# MCU.net
KiCad netlist of a schematic drawn in Altium Designer
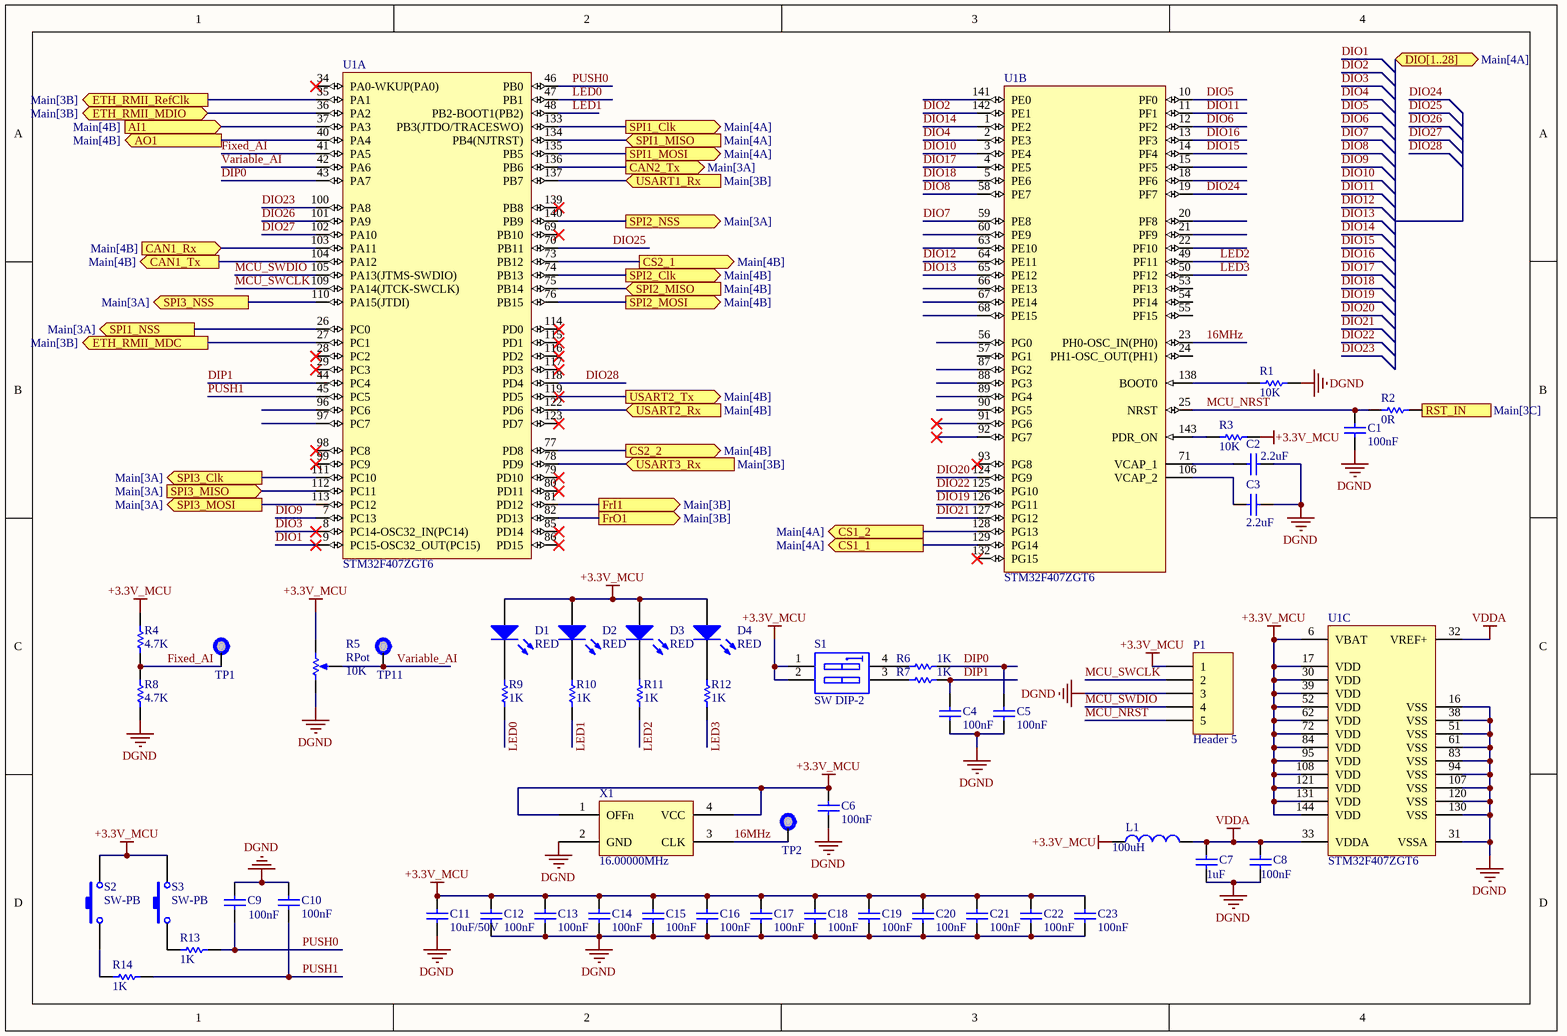
[diagram p0: MCU.SchDoc]

(export (version "E")
  (design (tool "Eeschema 10.0.6"))
  (components
    (comp (ref "C1")
      (value "100nF")
      (footprint "0603c")
      (description "LOW ESR")
      (fields (field (name "PUBLISHER") "Altium Limited"))
      (libsource (lib "Miscellaneous Devices") (part "Cap"))
    )
    (comp (ref "C2")
      (value "2.2uF")
      (footprint "0805C")
      (description "LOW ESR")
      (fields (field (name "PUBLISHER") "Altium Limited"))
      (libsource (lib "Miscellaneous Devices") (part "Cap"))
    )
    (comp (ref "C3")
      (value "2.2uF")
      (footprint "0805C")
      (description "LOW ESR")
      (fields (field (name "PUBLISHER") "Altium Limited"))
      (libsource (lib "Miscellaneous Devices") (part "Cap"))
    )
    (comp (ref "C4")
      (value "100nF")
      (footprint "0603c")
      (description "LOW ESR")
      (fields (field (name "PUBLISHER") "Altium Limited"))
      (libsource (lib "Miscellaneous Devices") (part "Cap"))
    )
    (comp (ref "C5")
      (value "100nF")
      (footprint "0603c")
      (description "LOW ESR")
      (fields (field (name "PUBLISHER") "Altium Limited"))
      (libsource (lib "Miscellaneous Devices") (part "Cap"))
    )
    (comp (ref "C6")
      (value "100nF")
      (footprint "0603C")
      (description "LOW ESR")
      (fields (field (name "PUBLISHER") "Altium Limited"))
      (libsource (lib "Miscellaneous Devices") (part "Cap"))
    )
    (comp (ref "C7")
      (value "1uF")
      (footprint "0805C")
      (description "LOW ESR")
      (fields (field (name "PUBLISHER") "Altium Limited"))
      (libsource (lib "Miscellaneous Devices") (part "Cap"))
    )
    (comp (ref "C8")
      (value "100nF")
      (footprint "0603C")
      (description "LOW ESR")
      (fields (field (name "PUBLISHER") "Altium Limited"))
      (libsource (lib "Miscellaneous Devices") (part "Cap"))
    )
    (comp (ref "C9")
      (value "100nF")
      (footprint "0603c")
      (description "LOW ESR")
      (fields (field (name "PUBLISHER") "Altium Limited"))
      (libsource (lib "Miscellaneous Devices") (part "Cap"))
    )
    (comp (ref "C10")
      (value "100nF")
      (footprint "0603c")
      (description "LOW ESR")
      (fields (field (name "PUBLISHER") "Altium Limited"))
      (libsource (lib "Miscellaneous Devices") (part "Cap"))
    )
    (comp (ref "C11")
      (value "10uF/50V")
      (footprint "1206C")
      (description "Capacitor")
      (fields (field (name "Comment") "CGA5L1X7R1H106K160AC") (field (name "PUBLISHER") "Altium Limited"))
      (libsource (lib "Miscellaneous Devices") (part "Cap"))
    )
    (comp (ref "C12")
      (value "100nF")
      (footprint "0603C")
      (description "Capacitor")
      (fields (field (name "Comment") "CGA3E2X7R1H104K080AA") (field (name "PUBLISHER") "Altium Limited"))
      (libsource (lib "Miscellaneous Devices") (part "Cap"))
    )
    (comp (ref "C13")
      (value "100nF")
      (footprint "0603C")
      (description "Capacitor")
      (fields (field (name "Comment") "CGA3E2X7R1H104K080AA") (field (name "PUBLISHER") "Altium Limited"))
      (libsource (lib "Miscellaneous Devices") (part "Cap"))
    )
    (comp (ref "C14")
      (value "100nF")
      (footprint "0603C")
      (description "Capacitor")
      (fields (field (name "Comment") "CGA3E2X7R1H104K080AA") (field (name "PUBLISHER") "Altium Limited"))
      (libsource (lib "Miscellaneous Devices") (part "Cap"))
    )
    (comp (ref "C15")
      (value "100nF")
      (footprint "0603C")
      (description "Capacitor")
      (fields (field (name "Comment") "CGA3E2X7R1H104K080AA") (field (name "PUBLISHER") "Altium Limited"))
      (libsource (lib "Miscellaneous Devices") (part "Cap"))
    )
    (comp (ref "C16")
      (value "100nF")
      (footprint "0603C")
      (description "Capacitor")
      (fields (field (name "Comment") "CGA3E2X7R1H104K080AA") (field (name "PUBLISHER") "Altium Limited"))
      (libsource (lib "Miscellaneous Devices") (part "Cap"))
    )
    (comp (ref "C17")
      (value "100nF")
      (footprint "0603C")
      (description "Capacitor")
      (fields (field (name "Comment") "CGA3E2X7R1H104K080AA") (field (name "PUBLISHER") "Altium Limited"))
      (libsource (lib "Miscellaneous Devices") (part "Cap"))
    )
    (comp (ref "C18")
      (value "100nF")
      (footprint "0603C")
      (description "Capacitor")
      (fields (field (name "Comment") "CGA3E2X7R1H104K080AA") (field (name "PUBLISHER") "Altium Limited"))
      (libsource (lib "Miscellaneous Devices") (part "Cap"))
    )
    (comp (ref "C19")
      (value "100nF")
      (footprint "0603C")
      (description "Capacitor")
      (fields (field (name "Comment") "CGA3E2X7R1H104K080AA") (field (name "PUBLISHER") "Altium Limited"))
      (libsource (lib "Miscellaneous Devices") (part "Cap"))
    )
    (comp (ref "C20")
      (value "100nF")
      (footprint "0603C")
      (description "Capacitor")
      (fields (field (name "Comment") "CGA3E2X7R1H104K080AA") (field (name "PUBLISHER") "Altium Limited"))
      (libsource (lib "Miscellaneous Devices") (part "Cap"))
    )
    (comp (ref "C21")
      (value "100nF")
      (footprint "0603C")
      (description "Capacitor")
      (fields (field (name "Comment") "CGA3E2X7R1H104K080AA") (field (name "PUBLISHER") "Altium Limited"))
      (libsource (lib "Miscellaneous Devices") (part "Cap"))
    )
    (comp (ref "C22")
      (value "100nF")
      (footprint "0603C")
      (description "Capacitor")
      (fields (field (name "Comment") "CGA3E2X7R1H104K080AA") (field (name "PUBLISHER") "Altium Limited"))
      (libsource (lib "Miscellaneous Devices") (part "Cap"))
    )
    (comp (ref "C23")
      (value "100nF")
      (footprint "0603C")
      (description "Capacitor")
      (fields (field (name "Comment") "CGA3E2X7R1H104K080AA") (field (name "PUBLISHER") "Altium Limited"))
      (libsource (lib "Miscellaneous Devices") (part "Cap"))
    )
    (comp (ref "D1")
      (value "RED")
      (footprint "0805LED")
      (description "Typical INFRARED GaAs LED")
      (fields (field (name "PUBLISHER") "Altium Limited"))
      (libsource (lib "Miscellaneous Devices") (part "LED0"))
    )
    (comp (ref "D2")
      (value "RED")
      (footprint "0805LED")
      (description "Typical INFRARED GaAs LED")
      (fields (field (name "PUBLISHER") "Altium Limited"))
      (libsource (lib "Miscellaneous Devices") (part "LED0"))
    )
    (comp (ref "D3")
      (value "RED")
      (footprint "0805LED")
      (description "Typical INFRARED GaAs LED")
      (fields (field (name "PUBLISHER") "Altium Limited"))
      (libsource (lib "Miscellaneous Devices") (part "LED0"))
    )
    (comp (ref "D4")
      (value "RED")
      (footprint "0805LED")
      (description "Typical INFRARED GaAs LED")
      (fields (field (name "PUBLISHER") "Altium Limited"))
      (libsource (lib "Miscellaneous Devices") (part "LED0"))
    )
    (comp (ref "L1")
      (value "100uH")
      (footprint "0805FB")
      (description "Inductor")
      (fields (field (name "PUBLISHER") "Altium Limited"))
      (libsource (lib "Miscellaneous Devices") (part "Inductor"))
    )
    (comp (ref "P1")
      (value "Header 5")
      (footprint "HDR1X5")
      (description "Header, 5-Pin")
      (fields (field (name "PUBLISHER") "Altium Limited"))
      (libsource (lib "Miscellaneous Connectors") (part "Header 5"))
    )
    (comp (ref "R1")
      (value "10K")
      (footprint "0805")
      (description "Resistor")
      (fields (field (name "Comment") "Res1") (field (name "PUBLISHER") "Altium Limited"))
      (libsource (lib "Miscellaneous Devices") (part "Res1"))
    )
    (comp (ref "R2")
      (value "0R")
      (footprint "0805")
      (description "Resistor")
      (fields (field (name "Comment") "Res1") (field (name "PUBLISHER") "Altium Limited"))
      (libsource (lib "Miscellaneous Devices") (part "Res1"))
    )
    (comp (ref "R3")
      (value "10K")
      (footprint "0805")
      (description "Resistor")
      (fields (field (name "Comment") "Res1") (field (name "PUBLISHER") "Altium Limited"))
      (libsource (lib "Miscellaneous Devices") (part "Res1"))
    )
    (comp (ref "R4")
      (value "4.7K")
      (footprint "0805")
      (description "Resistor")
      (fields (field (name "Comment") "Res1") (field (name "PUBLISHER") "Altium Limited"))
      (libsource (lib "Miscellaneous Devices") (part "Res1"))
    )
    (comp (ref "R5")
      (value "RPot")
      (footprint "POT-MULTITURN")
      (description "Potentiometer")
      (fields (field (name "ALTIUM_VALUE") "10K") (field (name "PUBLISHER") "Altium Limited"))
      (libsource (lib "Miscellaneous Devices") (part "RPot"))
    )
    (comp (ref "R6")
      (value "1K")
      (footprint "0805")
      (description "Resistor")
      (fields (field (name "Comment") "Res1") (field (name "PUBLISHER") "Altium Limited"))
      (libsource (lib "Miscellaneous Devices") (part "Res1"))
    )
    (comp (ref "R7")
      (value "1K")
      (footprint "0805")
      (description "Resistor")
      (fields (field (name "Comment") "Res1") (field (name "PUBLISHER") "Altium Limited"))
      (libsource (lib "Miscellaneous Devices") (part "Res1"))
    )
    (comp (ref "R8")
      (value "4.7K")
      (footprint "0805")
      (description "Resistor")
      (fields (field (name "Comment") "Res1") (field (name "PUBLISHER") "Altium Limited"))
      (libsource (lib "Miscellaneous Devices") (part "Res1"))
    )
    (comp (ref "R9")
      (value "1K")
      (footprint "0805")
      (description "Resistor")
      (fields (field (name "Comment") "Res1") (field (name "PUBLISHER") "Altium Limited"))
      (libsource (lib "Miscellaneous Devices") (part "Res1"))
    )
    (comp (ref "R10")
      (value "1K")
      (footprint "0805")
      (description "Resistor")
      (fields (field (name "Comment") "Res1") (field (name "PUBLISHER") "Altium Limited"))
      (libsource (lib "Miscellaneous Devices") (part "Res1"))
    )
    (comp (ref "R11")
      (value "1K")
      (footprint "0805")
      (description "Resistor")
      (fields (field (name "Comment") "Res1") (field (name "PUBLISHER") "Altium Limited"))
      (libsource (lib "Miscellaneous Devices") (part "Res1"))
    )
    (comp (ref "R12")
      (value "1K")
      (footprint "0805")
      (description "Resistor")
      (fields (field (name "Comment") "Res1") (field (name "PUBLISHER") "Altium Limited"))
      (libsource (lib "Miscellaneous Devices") (part "Res1"))
    )
    (comp (ref "R13")
      (value "1K")
      (footprint "0805")
      (description "Resistor")
      (fields (field (name "Comment") "Res1") (field (name "PUBLISHER") "Altium Limited"))
      (libsource (lib "Miscellaneous Devices") (part "Res1"))
    )
    (comp (ref "R14")
      (value "1K")
      (footprint "0805")
      (description "Resistor")
      (fields (field (name "Comment") "Res1") (field (name "PUBLISHER") "Altium Limited"))
      (libsource (lib "Miscellaneous Devices") (part "Res1"))
    )
    (comp (ref "S1")
      (value "SW DIP-2")
      (footprint "DIP-4")
      (description "DIP Switch, 2 Position, SPST")
      (fields (field (name "PUBLISHER") "Altium Limited"))
      (libsource (lib "Miscellaneous Devices") (part "SW DIP-2"))
    )
    (comp (ref "S2")
      (value "SW-PB")
      (footprint "PUSHBUTTON-SMD")
      (description "Switch")
      (fields (field (name "PUBLISHER") "Altium Limited"))
      (libsource (lib "Miscellaneous Devices") (part "SW-PB"))
    )
    (comp (ref "S3")
      (value "SW-PB")
      (footprint "PUSHBUTTON-SMD")
      (description "Switch")
      (fields (field (name "PUBLISHER") "Altium Limited"))
      (libsource (lib "Miscellaneous Devices") (part "SW-PB"))
    )
    (comp (ref "TP1") (value "TestPoint") (footprint "TP") (libsource (lib "SchlibV0.1") (part "TestPoint")))
    (comp (ref "TP2") (value "TestPoint") (footprint "TP") (libsource (lib "SchlibV0.1") (part "TestPoint")))
    (comp (ref "TP11") (value "TestPoint") (footprint "TP") (libsource (lib "SchlibV0.1") (part "TestPoint")))
    (comp (ref "U1")
      (value "STM32F407ZGT6")
      (footprint "STM-LQFP144_N")
      (fields (field (name "MANUFACTURER") "STMicroelectronics"))
      (libsource (lib "STMicroelectronics STM32 F4") (part "STM32F407ZGT6"))
    )
    (comp (ref "X1")
      (value "16.00000MHz")
      (footprint "OSC-SMT")
      (fields (field (name "Comment") "SG-8018CB 16.000000 MHZ TJHPA"))
      (libsource (lib "TMS320F2812-PGF") (part "Oscillator"))
    )
  )
  (nets
    (net (code "1") (name "+3.3V_MCU") (class "Default")
      (node (ref "C11") (pin "2") (pinfunction "2_2") (pintype "passive"))
      (node (ref "C12") (pin "1") (pinfunction "1_1") (pintype "passive"))
      (node (ref "C13") (pin "1") (pinfunction "1_1") (pintype "passive"))
      (node (ref "C14") (pin "1") (pinfunction "1_1") (pintype "passive"))
      (node (ref "C15") (pin "1") (pinfunction "1_1") (pintype "passive"))
      (node (ref "C16") (pin "1") (pinfunction "1_1") (pintype "passive"))
      (node (ref "C17") (pin "1") (pinfunction "1_1") (pintype "passive"))
      (node (ref "C18") (pin "1") (pinfunction "1_1") (pintype "passive"))
      (node (ref "C19") (pin "1") (pinfunction "1_1") (pintype "passive"))
      (node (ref "C20") (pin "1") (pinfunction "1_1") (pintype "passive"))
      (node (ref "C21") (pin "1") (pinfunction "1_1") (pintype "passive"))
      (node (ref "C22") (pin "1") (pinfunction "1_1") (pintype "passive"))
      (node (ref "C23") (pin "1") (pinfunction "1_1") (pintype "passive"))
      (node (ref "C6") (pin "1") (pinfunction "1_1") (pintype "passive"))
      (node (ref "D1") (pin "1") (pinfunction "A_1") (pintype "passive"))
      (node (ref "D2") (pin "1") (pinfunction "A_1") (pintype "passive"))
      (node (ref "D3") (pin "1") (pinfunction "A_1") (pintype "passive"))
      (node (ref "D4") (pin "1") (pinfunction "A_1") (pintype "passive"))
      (node (ref "L1") (pin "1") (pinfunction "1_1") (pintype "passive"))
      (node (ref "P1") (pin "1") (pinfunction "1_1") (pintype "passive"))
      (node (ref "R3") (pin "1") (pinfunction "1_1") (pintype "passive"))
      (node (ref "R4") (pin "2") (pinfunction "2_2") (pintype "passive"))
      (node (ref "R5") (pin "3") (pinfunction "BOT_3") (pintype "passive"))
      (node (ref "S1") (pin "1") (pinfunction "A1_1") (pintype "passive"))
      (node (ref "S1") (pin "2") (pinfunction "A2_2") (pintype "passive"))
      (node (ref "S2") (pin "2") (pinfunction "2_2") (pintype "passive"))
      (node (ref "S3") (pin "2") (pinfunction "2_2") (pintype "passive"))
      (node (ref "U1") (pin "108") (pinfunction "VDD_108") (pintype "power_in"))
      (node (ref "U1") (pin "121") (pinfunction "VDD_121") (pintype "power_in"))
      (node (ref "U1") (pin "131") (pinfunction "VDD_131") (pintype "power_in"))
      (node (ref "U1") (pin "144") (pinfunction "VDD_144") (pintype "power_in"))
      (node (ref "U1") (pin "17") (pinfunction "VDD_17") (pintype "power_in"))
      (node (ref "U1") (pin "30") (pinfunction "VDD_30") (pintype "power_in"))
      (node (ref "U1") (pin "39") (pinfunction "VDD_39") (pintype "power_in"))
      (node (ref "U1") (pin "52") (pinfunction "VDD_52") (pintype "power_in"))
      (node (ref "U1") (pin "6") (pinfunction "VBAT_6") (pintype "power_in"))
      (node (ref "U1") (pin "62") (pinfunction "VDD_62") (pintype "power_in"))
      (node (ref "U1") (pin "72") (pinfunction "VDD_72") (pintype "power_in"))
      (node (ref "U1") (pin "84") (pinfunction "VDD_84") (pintype "power_in"))
      (node (ref "U1") (pin "95") (pinfunction "VDD_95") (pintype "power_in"))
      (node (ref "X1") (pin "1") (pinfunction "OFFn_1") (pintype "passive"))
      (node (ref "X1") (pin "4") (pinfunction "VCC_4") (pintype "passive"))
    )
    (net (code "2") (name "/16MHz") (class "Default")
      (node (ref "TP2") (pin "1") (pintype "passive"))
      (node (ref "U1") (pin "23") (pinfunction "PH0-OSC_IN(PH0)_23") (pintype "bidirectional"))
      (node (ref "X1") (pin "3") (pinfunction "CLK_3") (pintype "passive"))
    )
    (net (code "3") (name "/AI1") (class "Default")
      (node (ref "U1") (pin "37") (pinfunction "PA3_37") (pintype "bidirectional"))
    )
    (net (code "4") (name "/AO1") (class "Default")
      (node (ref "U1") (pin "40") (pinfunction "PA4_40") (pintype "bidirectional"))
    )
    (net (code "5") (name "/CAN1_Rx") (class "Default")
      (node (ref "U1") (pin "103") (pinfunction "PA11_103") (pintype "bidirectional"))
    )
    (net (code "6") (name "/CAN1_Tx") (class "Default")
      (node (ref "U1") (pin "104") (pinfunction "PA12_104") (pintype "bidirectional"))
    )
    (net (code "7") (name "/CAN2_Tx") (class "Default")
      (node (ref "U1") (pin "136") (pinfunction "PB6_136") (pintype "bidirectional"))
    )
    (net (code "8") (name "/CS1_1") (class "Default")
      (node (ref "U1") (pin "129") (pinfunction "PG14_129") (pintype "bidirectional"))
    )
    (net (code "9") (name "/CS1_2") (class "Default")
      (node (ref "U1") (pin "128") (pinfunction "PG13_128") (pintype "bidirectional"))
    )
    (net (code "10") (name "/CS2_1") (class "Default")
      (node (ref "U1") (pin "73") (pinfunction "PB12_73") (pintype "bidirectional"))
    )
    (net (code "11") (name "/CS2_2") (class "Default")
      (node (ref "U1") (pin "77") (pinfunction "PD8_77") (pintype "bidirectional"))
    )
    (net (code "12") (name "/DIO1") (class "Default")
      (node (ref "U1") (pin "9") (pinfunction "PC15-OSC32_OUT(PC15)_9") (pintype "bidirectional+no_connect"))
    )
    (net (code "13") (name "/DIO2") (class "Default")
      (node (ref "U1") (pin "142") (pinfunction "PE1_142") (pintype "bidirectional"))
    )
    (net (code "14") (name "/DIO3") (class "Default")
      (node (ref "U1") (pin "8") (pinfunction "PC14-OSC32_IN(PC14)_8") (pintype "bidirectional+no_connect"))
    )
    (net (code "15") (name "/DIO4") (class "Default")
      (node (ref "U1") (pin "2") (pinfunction "PE3_2") (pintype "bidirectional"))
    )
    (net (code "16") (name "/DIO5") (class "Default")
      (node (ref "U1") (pin "10") (pinfunction "PF0_10") (pintype "bidirectional"))
    )
    (net (code "17") (name "/DIO6") (class "Default")
      (node (ref "U1") (pin "12") (pinfunction "PF2_12") (pintype "bidirectional"))
    )
    (net (code "18") (name "/DIO7") (class "Default")
      (node (ref "U1") (pin "59") (pinfunction "PE8_59") (pintype "bidirectional"))
    )
    (net (code "19") (name "/DIO8") (class "Default")
      (node (ref "U1") (pin "58") (pinfunction "PE7_58") (pintype "bidirectional"))
    )
    (net (code "20") (name "/DIO9") (class "Default")
      (node (ref "U1") (pin "7") (pinfunction "PC13_7") (pintype "bidirectional"))
    )
    (net (code "21") (name "/DIO10") (class "Default")
      (node (ref "U1") (pin "3") (pinfunction "PE4_3") (pintype "bidirectional"))
    )
    (net (code "22") (name "/DIO11") (class "Default")
      (node (ref "U1") (pin "11") (pinfunction "PF1_11") (pintype "bidirectional"))
    )
    (net (code "23") (name "/DIO12") (class "Default")
      (node (ref "U1") (pin "64") (pinfunction "PE11_64") (pintype "bidirectional"))
    )
    (net (code "24") (name "/DIO13") (class "Default")
      (node (ref "U1") (pin "65") (pinfunction "PE12_65") (pintype "bidirectional"))
    )
    (net (code "25") (name "/DIO14") (class "Default")
      (node (ref "U1") (pin "1") (pinfunction "PE2_1") (pintype "bidirectional"))
    )
    (net (code "26") (name "/DIO15") (class "Default")
      (node (ref "U1") (pin "14") (pinfunction "PF4_14") (pintype "bidirectional"))
    )
    (net (code "27") (name "/DIO16") (class "Default")
      (node (ref "U1") (pin "13") (pinfunction "PF3_13") (pintype "bidirectional"))
    )
    (net (code "28") (name "/DIO17") (class "Default")
      (node (ref "U1") (pin "4") (pinfunction "PE5_4") (pintype "bidirectional"))
    )
    (net (code "29") (name "/DIO18") (class "Default")
      (node (ref "U1") (pin "5") (pinfunction "PE6_5") (pintype "bidirectional"))
    )
    (net (code "30") (name "/DIO19") (class "Default")
      (node (ref "U1") (pin "126") (pinfunction "PG11_126") (pintype "bidirectional"))
    )
    (net (code "31") (name "/DIO20") (class "Default")
      (node (ref "U1") (pin "124") (pinfunction "PG9_124") (pintype "bidirectional"))
    )
    (net (code "32") (name "/DIO21") (class "Default")
      (node (ref "U1") (pin "127") (pinfunction "PG12_127") (pintype "bidirectional"))
    )
    (net (code "33") (name "/DIO22") (class "Default")
      (node (ref "U1") (pin "125") (pinfunction "PG10_125") (pintype "bidirectional"))
    )
    (net (code "34") (name "/DIO23") (class "Default")
      (node (ref "U1") (pin "100") (pinfunction "PA8_100") (pintype "bidirectional"))
    )
    (net (code "35") (name "/DIO24") (class "Default")
      (node (ref "U1") (pin "19") (pinfunction "PF7_19") (pintype "bidirectional"))
    )
    (net (code "36") (name "/DIO25") (class "Default")
      (node (ref "U1") (pin "70") (pinfunction "PB11_70") (pintype "bidirectional"))
    )
    (net (code "37") (name "/DIO26") (class "Default")
      (node (ref "U1") (pin "101") (pinfunction "PA9_101") (pintype "bidirectional"))
    )
    (net (code "38") (name "/DIO27") (class "Default")
      (node (ref "U1") (pin "102") (pinfunction "PA10_102") (pintype "bidirectional"))
    )
    (net (code "39") (name "/DIO28") (class "Default")
      (node (ref "U1") (pin "118") (pinfunction "PD4_118") (pintype "bidirectional"))
    )
    (net (code "41") (name "/DIP0") (class "Default")
      (node (ref "C5") (pin "1") (pinfunction "1_1") (pintype "passive"))
      (node (ref "R6") (pin "2") (pinfunction "2_2") (pintype "passive"))
      (node (ref "U1") (pin "43") (pinfunction "PA7_43") (pintype "bidirectional"))
    )
    (net (code "42") (name "/DIP1") (class "Default")
      (node (ref "C4") (pin "1") (pinfunction "1_1") (pintype "passive"))
      (node (ref "R7") (pin "2") (pinfunction "2_2") (pintype "passive"))
      (node (ref "U1") (pin "44") (pinfunction "PC4_44") (pintype "bidirectional"))
    )
    (net (code "43") (name "/ETH_RMII_MDC") (class "Default")
      (node (ref "U1") (pin "27") (pinfunction "PC1_27") (pintype "bidirectional"))
    )
    (net (code "44") (name "/ETH_RMII_MDIO") (class "Default")
      (node (ref "U1") (pin "36") (pinfunction "PA2_36") (pintype "bidirectional"))
    )
    (net (code "45") (name "/ETH_RMII_RefClk") (class "Default")
      (node (ref "U1") (pin "35") (pinfunction "PA1_35") (pintype "bidirectional"))
    )
    (net (code "46") (name "/Fixed_AI") (class "Default")
      (node (ref "R4") (pin "1") (pinfunction "1_1") (pintype "passive"))
      (node (ref "R8") (pin "2") (pinfunction "2_2") (pintype "passive"))
      (node (ref "TP1") (pin "1") (pintype "passive"))
      (node (ref "U1") (pin "41") (pinfunction "PA5_41") (pintype "bidirectional"))
    )
    (net (code "47") (name "/FrI1") (class "Default")
      (node (ref "U1") (pin "81") (pinfunction "PD12_81") (pintype "bidirectional"))
    )
    (net (code "48") (name "/FrO1") (class "Default")
      (node (ref "U1") (pin "82") (pinfunction "PD13_82") (pintype "bidirectional"))
    )
    (net (code "49") (name "/LED0") (class "Default")
      (node (ref "R9") (pin "1") (pinfunction "1_1") (pintype "passive"))
      (node (ref "U1") (pin "47") (pinfunction "PB1_47") (pintype "bidirectional"))
    )
    (net (code "50") (name "/LED1") (class "Default")
      (node (ref "R10") (pin "1") (pinfunction "1_1") (pintype "passive"))
      (node (ref "U1") (pin "48") (pinfunction "PB2-BOOT1(PB2)_48") (pintype "bidirectional"))
    )
    (net (code "51") (name "/LED2") (class "Default")
      (node (ref "R11") (pin "1") (pinfunction "1_1") (pintype "passive"))
      (node (ref "U1") (pin "49") (pinfunction "PF11_49") (pintype "bidirectional"))
    )
    (net (code "52") (name "/LED3") (class "Default")
      (node (ref "R12") (pin "1") (pinfunction "1_1") (pintype "passive"))
      (node (ref "U1") (pin "50") (pinfunction "PF12_50") (pintype "bidirectional"))
    )
    (net (code "53") (name "/MCU_NRST") (class "Default")
      (node (ref "C1") (pin "1") (pinfunction "1_1") (pintype "passive"))
      (node (ref "P1") (pin "5") (pinfunction "5_5") (pintype "passive"))
      (node (ref "R2") (pin "2") (pinfunction "2_2") (pintype "passive"))
      (node (ref "U1") (pin "25") (pinfunction "NRST_25") (pintype "bidirectional"))
    )
    (net (code "54") (name "/MCU_SWCLK") (class "Default")
      (node (ref "P1") (pin "2") (pinfunction "2_2") (pintype "passive"))
      (node (ref "U1") (pin "109") (pinfunction "PA14(JTCK-SWCLK)_109") (pintype "bidirectional"))
    )
    (net (code "55") (name "/MCU_SWDIO") (class "Default")
      (node (ref "P1") (pin "4") (pinfunction "4_4") (pintype "passive"))
      (node (ref "U1") (pin "105") (pinfunction "PA13(JTMS-SWDIO)_105") (pintype "bidirectional"))
    )
    (net (code "56") (name "/PUSH0") (class "Default")
      (node (ref "C9") (pin "2") (pinfunction "2_2") (pintype "passive"))
      (node (ref "R13") (pin "2") (pinfunction "2_2") (pintype "passive"))
      (node (ref "U1") (pin "46") (pinfunction "PB0_46") (pintype "bidirectional"))
    )
    (net (code "57") (name "/PUSH1") (class "Default")
      (node (ref "C10") (pin "2") (pinfunction "2_2") (pintype "passive"))
      (node (ref "R14") (pin "1") (pinfunction "1_1") (pintype "passive"))
      (node (ref "U1") (pin "45") (pinfunction "PC5_45") (pintype "bidirectional"))
    )
    (net (code "58") (name "/RST_IN") (class "Default")
      (node (ref "R2") (pin "1") (pinfunction "1_1") (pintype "passive"))
    )
    (net (code "59") (name "/SPI1_Clk") (class "Default")
      (node (ref "U1") (pin "133") (pinfunction "PB3(JTDO/TRACESWO)_133") (pintype "bidirectional"))
    )
    (net (code "60") (name "/SPI1_MISO") (class "Default")
      (node (ref "U1") (pin "134") (pinfunction "PB4(NJTRST)_134") (pintype "bidirectional"))
    )
    (net (code "61") (name "/SPI1_MOSI") (class "Default")
      (node (ref "U1") (pin "135") (pinfunction "PB5_135") (pintype "bidirectional"))
    )
    (net (code "62") (name "/SPI1_NSS") (class "Default")
      (node (ref "U1") (pin "26") (pinfunction "PC0_26") (pintype "bidirectional"))
    )
    (net (code "63") (name "/SPI2_Clk") (class "Default")
      (node (ref "U1") (pin "74") (pinfunction "PB13_74") (pintype "bidirectional"))
    )
    (net (code "64") (name "/SPI2_MISO") (class "Default")
      (node (ref "U1") (pin "75") (pinfunction "PB14_75") (pintype "bidirectional"))
    )
    (net (code "65") (name "/SPI2_MOSI") (class "Default")
      (node (ref "U1") (pin "76") (pinfunction "PB15_76") (pintype "bidirectional"))
    )
    (net (code "66") (name "/SPI2_NSS") (class "Default")
      (node (ref "U1") (pin "140") (pinfunction "PB9_140") (pintype "bidirectional"))
    )
    (net (code "67") (name "/SPI3_Clk") (class "Default")
      (node (ref "U1") (pin "111") (pinfunction "PC10_111") (pintype "bidirectional"))
    )
    (net (code "68") (name "/SPI3_MISO") (class "Default")
      (node (ref "U1") (pin "112") (pinfunction "PC11_112") (pintype "bidirectional"))
    )
    (net (code "69") (name "/SPI3_MOSI") (class "Default")
      (node (ref "U1") (pin "113") (pinfunction "PC12_113") (pintype "bidirectional"))
    )
    (net (code "70") (name "/SPI3_NSS") (class "Default")
      (node (ref "U1") (pin "110") (pinfunction "PA15(JTDI)_110") (pintype "bidirectional"))
    )
    (net (code "71") (name "/USART1_Rx") (class "Default")
      (node (ref "U1") (pin "137") (pinfunction "PB7_137") (pintype "bidirectional"))
    )
    (net (code "72") (name "/USART2_Rx") (class "Default")
      (node (ref "U1") (pin "122") (pinfunction "PD6_122") (pintype "bidirectional"))
    )
    (net (code "73") (name "/USART2_Tx") (class "Default")
      (node (ref "U1") (pin "119") (pinfunction "PD5_119") (pintype "bidirectional+no_connect"))
    )
    (net (code "74") (name "/USART3_Rx") (class "Default")
      (node (ref "U1") (pin "78") (pinfunction "PD9_78") (pintype "bidirectional"))
    )
    (net (code "75") (name "/Variable_AI") (class "Default")
      (node (ref "R5") (pin "2") (pinfunction "TAP_2") (pintype "passive"))
      (node (ref "TP11") (pin "1") (pintype "passive"))
      (node (ref "U1") (pin "42") (pinfunction "PA6_42") (pintype "bidirectional"))
    )
    (net (code "76") (name "DGND") (class "Default")
      (node (ref "C1") (pin "2") (pinfunction "2_2") (pintype "passive"))
      (node (ref "C10") (pin "1") (pinfunction "1_1") (pintype "passive"))
      (node (ref "C11") (pin "1") (pinfunction "1_1") (pintype "passive"))
      (node (ref "C12") (pin "2") (pinfunction "2_2") (pintype "passive"))
      (node (ref "C13") (pin "2") (pinfunction "2_2") (pintype "passive"))
      (node (ref "C14") (pin "2") (pinfunction "2_2") (pintype "passive"))
      (node (ref "C15") (pin "2") (pinfunction "2_2") (pintype "passive"))
      (node (ref "C16") (pin "2") (pinfunction "2_2") (pintype "passive"))
      (node (ref "C17") (pin "2") (pinfunction "2_2") (pintype "passive"))
      (node (ref "C18") (pin "2") (pinfunction "2_2") (pintype "passive"))
      (node (ref "C19") (pin "2") (pinfunction "2_2") (pintype "passive"))
      (node (ref "C2") (pin "2") (pinfunction "2_2") (pintype "passive"))
      (node (ref "C20") (pin "2") (pinfunction "2_2") (pintype "passive"))
      (node (ref "C21") (pin "2") (pinfunction "2_2") (pintype "passive"))
      (node (ref "C22") (pin "2") (pinfunction "2_2") (pintype "passive"))
      (node (ref "C23") (pin "2") (pinfunction "2_2") (pintype "passive"))
      (node (ref "C3") (pin "2") (pinfunction "2_2") (pintype "passive"))
      (node (ref "C4") (pin "2") (pinfunction "2_2") (pintype "passive"))
      (node (ref "C5") (pin "2") (pinfunction "2_2") (pintype "passive"))
      (node (ref "C6") (pin "2") (pinfunction "2_2") (pintype "passive"))
      (node (ref "C7") (pin "1") (pinfunction "1_1") (pintype "passive"))
      (node (ref "C8") (pin "1") (pinfunction "1_1") (pintype "passive"))
      (node (ref "C9") (pin "1") (pinfunction "1_1") (pintype "passive"))
      (node (ref "P1") (pin "3") (pinfunction "3_3") (pintype "passive"))
      (node (ref "R1") (pin "1") (pinfunction "1_1") (pintype "passive"))
      (node (ref "R5") (pin "1") (pinfunction "TOP_1") (pintype "passive"))
      (node (ref "R8") (pin "1") (pinfunction "1_1") (pintype "passive"))
      (node (ref "U1") (pin "107") (pinfunction "VSS_107") (pintype "power_in"))
      (node (ref "U1") (pin "120") (pinfunction "VSS_120") (pintype "power_in"))
      (node (ref "U1") (pin "130") (pinfunction "VSS_130") (pintype "power_in"))
      (node (ref "U1") (pin "16") (pinfunction "VSS_16") (pintype "power_in"))
      (node (ref "U1") (pin "31") (pinfunction "VSSA_31") (pintype "power_in"))
      (node (ref "U1") (pin "38") (pinfunction "VSS_38") (pintype "power_in"))
      (node (ref "U1") (pin "51") (pinfunction "VSS_51") (pintype "power_in"))
      (node (ref "U1") (pin "61") (pinfunction "VSS_61") (pintype "power_in"))
      (node (ref "U1") (pin "83") (pinfunction "VSS_83") (pintype "power_in"))
      (node (ref "U1") (pin "94") (pinfunction "VSS_94") (pintype "power_in"))
      (node (ref "X1") (pin "2") (pinfunction "GND_2") (pintype "passive"))
    )
    (net (code "77") (name "Net-(D1-K)") (class "Default")
      (node (ref "D1") (pin "2") (pinfunction "K_2") (pintype "passive"))
      (node (ref "R9") (pin "2") (pinfunction "2_2") (pintype "passive"))
    )
    (net (code "78") (name "Net-(D2-K)") (class "Default")
      (node (ref "D2") (pin "2") (pinfunction "K_2") (pintype "passive"))
      (node (ref "R10") (pin "2") (pinfunction "2_2") (pintype "passive"))
    )
    (net (code "79") (name "Net-(D3-K)") (class "Default")
      (node (ref "D3") (pin "2") (pinfunction "K_2") (pintype "passive"))
      (node (ref "R11") (pin "2") (pinfunction "2_2") (pintype "passive"))
    )
    (net (code "80") (name "Net-(D4-K)") (class "Default")
      (node (ref "D4") (pin "2") (pinfunction "K_2") (pintype "passive"))
      (node (ref "R12") (pin "2") (pinfunction "2_2") (pintype "passive"))
    )
    (net (code "81") (name "Net-(R13-Pad1)") (class "Default")
      (node (ref "R13") (pin "1") (pinfunction "1_1") (pintype "passive"))
      (node (ref "S3") (pin "1") (pinfunction "1_1") (pintype "passive"))
    )
    (net (code "82") (name "Net-(R14-Pad2)") (class "Default")
      (node (ref "R14") (pin "2") (pinfunction "2_2") (pintype "passive"))
      (node (ref "S2") (pin "1") (pinfunction "1_1") (pintype "passive"))
    )
    (net (code "83") (name "Net-(S1-B1)") (class "Default")
      (node (ref "R6") (pin "1") (pinfunction "1_1") (pintype "passive"))
      (node (ref "S1") (pin "4") (pinfunction "B1_4") (pintype "passive"))
    )
    (net (code "84") (name "Net-(S1-B2)") (class "Default")
      (node (ref "R7") (pin "1") (pinfunction "1_1") (pintype "passive"))
      (node (ref "S1") (pin "3") (pinfunction "B2_3") (pintype "passive"))
    )
    (net (code "85") (name "Net-(U1B-BOOT0)") (class "Default")
      (node (ref "R1") (pin "2") (pinfunction "2_2") (pintype "passive"))
      (node (ref "U1") (pin "138") (pinfunction "BOOT0_138") (pintype "input"))
    )
    (net (code "86") (name "Net-(U1B-PDR_ON)") (class "Default")
      (node (ref "R3") (pin "2") (pinfunction "2_2") (pintype "passive"))
      (node (ref "U1") (pin "143") (pinfunction "PDR_ON_143") (pintype "input"))
    )
    (net (code "87") (name "Net-(U1B-VCAP_1)") (class "Default")
      (node (ref "C2") (pin "1") (pinfunction "1_1") (pintype "passive"))
      (node (ref "U1") (pin "71") (pinfunction "VCAP_1_71") (pintype "power_in"))
    )
    (net (code "88") (name "Net-(U1B-VCAP_2)") (class "Default")
      (node (ref "C3") (pin "1") (pinfunction "1_1") (pintype "passive"))
      (node (ref "U1") (pin "106") (pinfunction "VCAP_2_106") (pintype "power_in"))
    )
    (net (code "89") (name "VDDA") (class "Default")
      (node (ref "C7") (pin "2") (pinfunction "2_2") (pintype "passive"))
      (node (ref "C8") (pin "2") (pinfunction "2_2") (pintype "passive"))
      (node (ref "L1") (pin "2") (pinfunction "2_2") (pintype "passive"))
      (node (ref "U1") (pin "32") (pinfunction "VREF+_32") (pintype "power_in"))
      (node (ref "U1") (pin "33") (pinfunction "VDDA_33") (pintype "power_in"))
    )
    (net (code "90") (name "unconnected-(U1A-PA0-WKUP(PA0)-Pad34)") (class "Default")
      (node (ref "U1") (pin "34") (pinfunction "PA0-WKUP(PA0)_34") (pintype "bidirectional+no_connect"))
    )
    (net (code "91") (name "unconnected-(U1A-PB8-Pad139)") (class "Default")
      (node (ref "U1") (pin "139") (pinfunction "PB8_139") (pintype "bidirectional+no_connect"))
    )
    (net (code "92") (name "unconnected-(U1A-PB10-Pad69)") (class "Default")
      (node (ref "U1") (pin "69") (pinfunction "PB10_69") (pintype "bidirectional+no_connect"))
    )
    (net (code "93") (name "unconnected-(U1A-PC2-Pad28)") (class "Default")
      (node (ref "U1") (pin "28") (pinfunction "PC2_28") (pintype "bidirectional+no_connect"))
    )
    (net (code "94") (name "unconnected-(U1A-PC3-Pad29)") (class "Default")
      (node (ref "U1") (pin "29") (pinfunction "PC3_29") (pintype "bidirectional+no_connect"))
    )
    (net (code "95") (name "unconnected-(U1A-PC6-Pad96)") (class "Default")
      (node (ref "U1") (pin "96") (pinfunction "PC6_96") (pintype "bidirectional"))
    )
    (net (code "96") (name "unconnected-(U1A-PC7-Pad97)") (class "Default")
      (node (ref "U1") (pin "97") (pinfunction "PC7_97") (pintype "bidirectional"))
    )
    (net (code "97") (name "unconnected-(U1A-PC8-Pad98)") (class "Default")
      (node (ref "U1") (pin "98") (pinfunction "PC8_98") (pintype "bidirectional+no_connect"))
    )
    (net (code "98") (name "unconnected-(U1A-PC9-Pad99)") (class "Default")
      (node (ref "U1") (pin "99") (pinfunction "PC9_99") (pintype "bidirectional+no_connect"))
    )
    (net (code "99") (name "unconnected-(U1A-PD0-Pad114)") (class "Default")
      (node (ref "U1") (pin "114") (pinfunction "PD0_114") (pintype "bidirectional+no_connect"))
    )
    (net (code "100") (name "unconnected-(U1A-PD1-Pad115)") (class "Default")
      (node (ref "U1") (pin "115") (pinfunction "PD1_115") (pintype "bidirectional+no_connect"))
    )
    (net (code "101") (name "unconnected-(U1A-PD2-Pad116)") (class "Default")
      (node (ref "U1") (pin "116") (pinfunction "PD2_116") (pintype "bidirectional+no_connect"))
    )
    (net (code "102") (name "unconnected-(U1A-PD3-Pad117)") (class "Default")
      (node (ref "U1") (pin "117") (pinfunction "PD3_117") (pintype "bidirectional+no_connect"))
    )
    (net (code "103") (name "unconnected-(U1A-PD7-Pad123)") (class "Default")
      (node (ref "U1") (pin "123") (pinfunction "PD7_123") (pintype "bidirectional+no_connect"))
    )
    (net (code "104") (name "unconnected-(U1A-PD10-Pad79)") (class "Default")
      (node (ref "U1") (pin "79") (pinfunction "PD10_79") (pintype "bidirectional+no_connect"))
    )
    (net (code "105") (name "unconnected-(U1A-PD11-Pad80)") (class "Default")
      (node (ref "U1") (pin "80") (pinfunction "PD11_80") (pintype "bidirectional+no_connect"))
    )
    (net (code "106") (name "unconnected-(U1A-PD14-Pad85)") (class "Default")
      (node (ref "U1") (pin "85") (pinfunction "PD14_85") (pintype "bidirectional+no_connect"))
    )
    (net (code "107") (name "unconnected-(U1A-PD15-Pad86)") (class "Default")
      (node (ref "U1") (pin "86") (pinfunction "PD15_86") (pintype "bidirectional+no_connect"))
    )
    (net (code "108") (name "unconnected-(U1B-PE0-Pad141)") (class "Default")
      (node (ref "U1") (pin "141") (pinfunction "PE0_141") (pintype "bidirectional"))
    )
    (net (code "109") (name "unconnected-(U1B-PE9-Pad60)") (class "Default")
      (node (ref "U1") (pin "60") (pinfunction "PE9_60") (pintype "bidirectional"))
    )
    (net (code "110") (name "unconnected-(U1B-PE10-Pad63)") (class "Default")
      (node (ref "U1") (pin "63") (pinfunction "PE10_63") (pintype "bidirectional"))
    )
    (net (code "111") (name "unconnected-(U1B-PE13-Pad66)") (class "Default")
      (node (ref "U1") (pin "66") (pinfunction "PE13_66") (pintype "bidirectional"))
    )
    (net (code "112") (name "unconnected-(U1B-PE14-Pad67)") (class "Default")
      (node (ref "U1") (pin "67") (pinfunction "PE14_67") (pintype "bidirectional"))
    )
    (net (code "113") (name "unconnected-(U1B-PE15-Pad68)") (class "Default")
      (node (ref "U1") (pin "68") (pinfunction "PE15_68") (pintype "bidirectional"))
    )
    (net (code "114") (name "unconnected-(U1B-PF5-Pad15)") (class "Default")
      (node (ref "U1") (pin "15") (pinfunction "PF5_15") (pintype "bidirectional"))
    )
    (net (code "115") (name "unconnected-(U1B-PF6-Pad18)") (class "Default")
      (node (ref "U1") (pin "18") (pinfunction "PF6_18") (pintype "bidirectional"))
    )
    (net (code "116") (name "unconnected-(U1B-PF8-Pad20)") (class "Default")
      (node (ref "U1") (pin "20") (pinfunction "PF8_20") (pintype "bidirectional"))
    )
    (net (code "117") (name "unconnected-(U1B-PF9-Pad21)") (class "Default")
      (node (ref "U1") (pin "21") (pinfunction "PF9_21") (pintype "bidirectional"))
    )
    (net (code "118") (name "unconnected-(U1B-PF10-Pad22)") (class "Default")
      (node (ref "U1") (pin "22") (pinfunction "PF10_22") (pintype "bidirectional"))
    )
    (net (code "119") (name "unconnected-(U1B-PF13-Pad53)") (class "Default")
      (node (ref "U1") (pin "53") (pinfunction "PF13_53") (pintype "bidirectional"))
    )
    (net (code "120") (name "unconnected-(U1B-PF14-Pad54)") (class "Default")
      (node (ref "U1") (pin "54") (pinfunction "PF14_54") (pintype "bidirectional"))
    )
    (net (code "121") (name "unconnected-(U1B-PF15-Pad55)") (class "Default")
      (node (ref "U1") (pin "55") (pinfunction "PF15_55") (pintype "bidirectional"))
    )
    (net (code "122") (name "unconnected-(U1B-PG0-Pad56)") (class "Default")
      (node (ref "U1") (pin "56") (pinfunction "PG0_56") (pintype "bidirectional"))
    )
    (net (code "123") (name "unconnected-(U1B-PG1-Pad57)") (class "Default")
      (node (ref "U1") (pin "57") (pinfunction "PG1_57") (pintype "bidirectional"))
    )
    (net (code "124") (name "unconnected-(U1B-PG2-Pad87)") (class "Default")
      (node (ref "U1") (pin "87") (pinfunction "PG2_87") (pintype "bidirectional"))
    )
    (net (code "125") (name "unconnected-(U1B-PG3-Pad88)") (class "Default")
      (node (ref "U1") (pin "88") (pinfunction "PG3_88") (pintype "bidirectional"))
    )
    (net (code "126") (name "unconnected-(U1B-PG4-Pad89)") (class "Default")
      (node (ref "U1") (pin "89") (pinfunction "PG4_89") (pintype "bidirectional"))
    )
    (net (code "127") (name "unconnected-(U1B-PG5-Pad90)") (class "Default")
      (node (ref "U1") (pin "90") (pinfunction "PG5_90") (pintype "bidirectional"))
    )
    (net (code "128") (name "unconnected-(U1B-PG6-Pad91)") (class "Default")
      (node (ref "U1") (pin "91") (pinfunction "PG6_91") (pintype "bidirectional+no_connect"))
    )
    (net (code "129") (name "unconnected-(U1B-PG7-Pad92)") (class "Default")
      (node (ref "U1") (pin "92") (pinfunction "PG7_92") (pintype "bidirectional+no_connect"))
    )
    (net (code "130") (name "unconnected-(U1B-PG8-Pad93)") (class "Default")
      (node (ref "U1") (pin "93") (pinfunction "PG8_93") (pintype "bidirectional+no_connect"))
    )
    (net (code "131") (name "unconnected-(U1B-PG15-Pad132)") (class "Default")
      (node (ref "U1") (pin "132") (pinfunction "PG15_132") (pintype "bidirectional+no_connect"))
    )
    (net (code "132") (name "unconnected-(U1B-PH1-OSC_OUT(PH1)-Pad24)") (class "Default")
      (node (ref "U1") (pin "24") (pinfunction "PH1-OSC_OUT(PH1)_24") (pintype "bidirectional"))
    )
  )
)
